# LaserController.net
KiCad netlist of a schematic drawn in Altium Designer
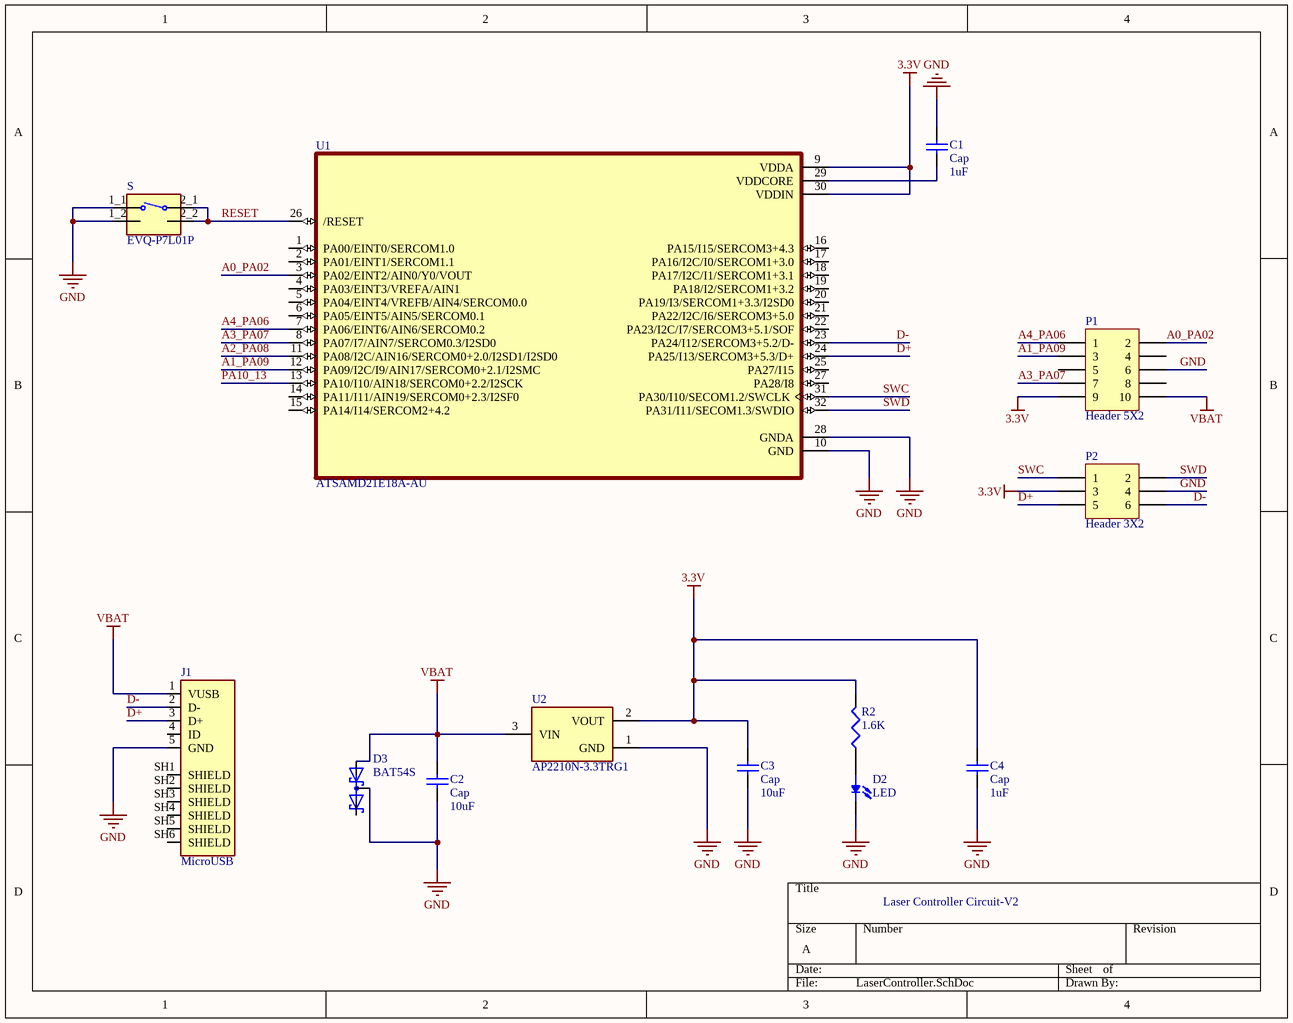
[diagram p0: LaserController.SchDoc]

(export (version "E")
  (design (tool "Eeschema 10.0.6"))
  (components
    (comp (ref "C1")
      (value "Cap")
      (footprint "6-0805_M")
      (description "Capacitor")
      (fields (field (name "ALTIUM_VALUE") "1uF") (field (name "PUBLISHER") "Altium Limited"))
      (libsource (lib "Miscellaneous Devices") (part "Cap"))
    )
    (comp (ref "C2")
      (value "Cap")
      (footprint "6-0805_M")
      (description "Capacitor")
      (fields (field (name "ALTIUM_VALUE") "10uF") (field (name "PUBLISHER") "Altium Limited"))
      (libsource (lib "Miscellaneous Devices") (part "Cap"))
    )
    (comp (ref "C3")
      (value "Cap")
      (footprint "6-0805_M")
      (description "Capacitor")
      (fields (field (name "ALTIUM_VALUE") "10uF") (field (name "PUBLISHER") "Altium Limited"))
      (libsource (lib "Miscellaneous Devices") (part "Cap"))
    )
    (comp (ref "C4")
      (value "Cap")
      (footprint "6-0805_M")
      (description "Capacitor")
      (fields (field (name "ALTIUM_VALUE") "1uF") (field (name "PUBLISHER") "Altium Limited"))
      (libsource (lib "Miscellaneous Devices") (part "Cap"))
    )
    (comp (ref "D2")
      (value "LED")
      (footprint "DIO_SMLMN2WB1CW1C")
      (description "White LED Indication - Discrete 2.9V 0805 _2012 Metric_")
      (fields (field (name "MP") "SMLMN2WB1CW1C") (field (name "MF") "Rohm Semiconductor"))
      (libsource (lib "SMLMN2WB1CW1C") (part "SMLMN2WB1CW1C"))
    )
    (comp (ref "D3")
      (value "BAT54S")
      (footprint "SnapEDApcb:SOT23")
      (description "Diode Array 1 Pair Series Connection Schottky 30V 200mA Surface Mount TO-236-3, SC-59, SOT-23-3")
      (fields (field (name "MF") "ON Semiconductor"))
      (libsource (lib "BAT54S") (part "BAT54S"))
    )
    (comp (ref "J1")
      (value "MicroUSB")
      (footprint "AMPHENOL_10118192-0001LF")
      (description "USB - micro B USB 2.0 Receptacle Connector 5 Position Surface Mount, Right Angle")
      (fields (field (name "MP") "10118192-0001LF") (field (name "MF") "Amphenol ICC"))
      (libsource (lib "MicroUSB_2") (part "10118192-0001LF"))
    )
    (comp (ref "P1")
      (value "Header 5X2")
      (footprint "HDR2X5")
      (description "Header, 5-Pin, Dual row")
      (fields (field (name "PUBLISHER") "Altium Limited"))
      (libsource (lib "Miscellaneous Connectors") (part "Header 5X2"))
    )
    (comp (ref "P2")
      (value "Header 3X2")
      (footprint "HDR2X3")
      (description "Header, 3-Pin, Dual row")
      (fields (field (name "PUBLISHER") "Altium Limited"))
      (libsource (lib "Miscellaneous Connectors") (part "Header 3X2"))
    )
    (comp (ref "R2")
      (value "1.6K")
      (footprint "6-0805_M")
      (description "Resistor")
      (fields (field (name "PUBLISHER") "Altium Limited"))
      (libsource (lib "Miscellaneous Devices") (part "Res3"))
    )
    (comp (ref "S")
      (value "EVQ-P7L01P")
      (footprint "SW_EVQ-P7L01P")
      (description "Tactile Switch SPST-NO Side Actuated Surface Mount, Right Angle")
      (fields
        (field (name "DIGI-KEY_PART_NUMBER") "P16769CT-ND")
        (field (name "MF") "Panasonic Electronic Components")
      )
      (libsource (lib "EVQ-P7L01P") (part "EVQ-P7L01P"))
    )
    (comp (ref "U1")
      (value "ATSAMD21E18A-AU")
      (footprint "QFP80P900X900X120-32N:QFP80P900X900X120-32N")
      (description "ARM庐 Cortex庐-M0+ SAM D21E Microcontroller IC 32-Bit 48MHz 256KB (256K x 8) FLASH 32-TQFP (7x7)")
      (fields (field (name "MF") "Microchip"))
      (libsource (lib "SAMD21") (part "ATSAMD21E18A-AU"))
    )
    (comp (ref "U2")
      (value "AP2210N-3.3TRG1")
      (footprint "SOT95P280X145-3N")
      (description "Linear Voltage Regulator IC 1 Output 300mA SOT-23-3")
      (fields (field (name "MF") "Diodes Inc."))
      (libsource (lib "AP2210N-3.3TRG1") (part "AP2210N-3.3TRG1"))
    )
  )
  (nets
    (net (code "1") (name "/A0_PA02") (class "Default")
      (node (ref "P1") (pin "2") (pinfunction "2_2") (pintype "passive"))
      (node (ref "U1") (pin "3") (pinfunction "PA02/EINT2/AIN0/Y0/VOUT_3") (pintype "bidirectional"))
    )
    (net (code "2") (name "/A1_PA09") (class "Default")
      (node (ref "P1") (pin "3") (pinfunction "3_3") (pintype "passive"))
      (node (ref "U1") (pin "12") (pinfunction "PA09/I2C/I9/AIN17/SERCOM0+2.1/I2SMC_12") (pintype "bidirectional"))
    )
    (net (code "3") (name "/A2_PA08") (class "Default")
      (node (ref "U1") (pin "11") (pinfunction "PA08/I2C/AIN16/SERCOM0+2.0/I2SD1/I2SD0_11") (pintype "bidirectional"))
    )
    (net (code "4") (name "/A3_PA07") (class "Default")
      (node (ref "P1") (pin "7") (pinfunction "7_7") (pintype "passive"))
      (node (ref "U1") (pin "8") (pinfunction "PA07/I7/AIN7/SERCOM0.3/I2SD0_8") (pintype "bidirectional"))
    )
    (net (code "5") (name "/A4_PA06") (class "Default")
      (node (ref "P1") (pin "1") (pinfunction "1_1") (pintype "passive"))
      (node (ref "U1") (pin "7") (pinfunction "PA06/EINT6/AIN6/SERCOM0.2_7") (pintype "bidirectional"))
    )
    (net (code "6") (name "/D+") (class "Default")
      (node (ref "J1") (pin "3") (pinfunction "D+_3") (pintype "passive"))
      (node (ref "P2") (pin "5") (pinfunction "5_5") (pintype "passive"))
      (node (ref "U1") (pin "24") (pinfunction "PA25/I13/SERCOM3+5.3/D+_24") (pintype "bidirectional"))
    )
    (net (code "7") (name "/D-") (class "Default")
      (node (ref "J1") (pin "2") (pinfunction "D-_2") (pintype "passive"))
      (node (ref "P2") (pin "6") (pinfunction "6_6") (pintype "passive"))
      (node (ref "U1") (pin "23") (pinfunction "PA24/I12/SERCOM3+5.2/D-_23") (pintype "bidirectional"))
    )
    (net (code "8") (name "/PA10_13") (class "Default")
      (node (ref "U1") (pin "13") (pinfunction "PA10/I10/AIN18/SERCOM0+2.2/I2SCK_13") (pintype "bidirectional"))
    )
    (net (code "9") (name "/RESET") (class "Default")
      (node (ref "S") (pin "2_1") (pinfunction "2_2_1") (pintype "passive"))
      (node (ref "S") (pin "2_2") (pinfunction "2_2_2") (pintype "passive"))
      (node (ref "U1") (pin "26") (pinfunction "/RESET_26") (pintype "bidirectional"))
    )
    (net (code "10") (name "/SWC") (class "Default")
      (node (ref "P2") (pin "1") (pinfunction "1_1") (pintype "passive"))
      (node (ref "U1") (pin "31") (pinfunction "PA30/I10/SECOM1.2/SWCLK_31") (pintype "bidirectional"))
    )
    (net (code "11") (name "/SWD") (class "Default")
      (node (ref "P2") (pin "2") (pinfunction "2_2") (pintype "passive"))
      (node (ref "U1") (pin "32") (pinfunction "PA31/I11/SECOM1.3/SWDIO_32") (pintype "bidirectional"))
    )
    (net (code "12") (name "3.3V") (class "Default")
      (node (ref "C3") (pin "2") (pinfunction "2_2") (pintype "passive"))
      (node (ref "C4") (pin "2") (pinfunction "2_2") (pintype "passive"))
      (node (ref "P1") (pin "9") (pinfunction "9_9") (pintype "passive"))
      (node (ref "P2") (pin "3") (pinfunction "3_3") (pintype "passive"))
      (node (ref "R2") (pin "2") (pinfunction "2_2") (pintype "passive"))
      (node (ref "U1") (pin "30") (pinfunction "VDDIN_30") (pintype "power_in"))
      (node (ref "U1") (pin "9") (pinfunction "VDDA_9") (pintype "power_in"))
      (node (ref "U2") (pin "2") (pinfunction "VOUT_2") (pintype "passive"))
    )
    (net (code "13") (name "GND") (class "Default")
      (node (ref "C1") (pin "2") (pinfunction "2_2") (pintype "passive"))
      (node (ref "C2") (pin "1") (pinfunction "1_1") (pintype "passive"))
      (node (ref "C3") (pin "1") (pinfunction "1_1") (pintype "passive"))
      (node (ref "C4") (pin "1") (pinfunction "1_1") (pintype "passive"))
      (node (ref "D2") (pin "C") (pinfunction "C_C") (pintype "passive"))
      (node (ref "D3") (pin "3") (pinfunction "K1A2_3") (pintype "passive"))
      (node (ref "J1") (pin "5") (pinfunction "GND_5") (pintype "passive"))
      (node (ref "P1") (pin "6") (pinfunction "6_6") (pintype "passive"))
      (node (ref "P2") (pin "4") (pinfunction "4_4") (pintype "passive"))
      (node (ref "S") (pin "1_1") (pinfunction "1_1_1") (pintype "passive"))
      (node (ref "S") (pin "1_2") (pinfunction "1_1_2") (pintype "passive"))
      (node (ref "U1") (pin "10") (pinfunction "GND_10") (pintype "power_in"))
      (node (ref "U1") (pin "28") (pinfunction "GNDA_28") (pintype "power_in"))
      (node (ref "U2") (pin "1") (pinfunction "GND_1") (pintype "passive"))
    )
    (net (code "14") (name "Net-(D2-PadA)") (class "Default")
      (node (ref "D2") (pin "A") (pinfunction "A_A") (pintype "passive"))
      (node (ref "R2") (pin "1") (pinfunction "1_1") (pintype "passive"))
    )
    (net (code "15") (name "Net-(U1-VDDCORE)") (class "Default")
      (node (ref "C1") (pin "1") (pinfunction "1_1") (pintype "passive"))
      (node (ref "U1") (pin "29") (pinfunction "VDDCORE_29") (pintype "power_in"))
    )
    (net (code "16") (name "VBAT") (class "Default")
      (node (ref "C2") (pin "2") (pinfunction "2_2") (pintype "passive"))
      (node (ref "D3") (pin "1") (pinfunction "A1_1") (pintype "passive"))
      (node (ref "J1") (pin "1") (pinfunction "VUSB_1") (pintype "passive"))
      (node (ref "P1") (pin "10") (pinfunction "10_10") (pintype "passive"))
      (node (ref "U2") (pin "3") (pinfunction "VIN_3") (pintype "passive"))
    )
    (net (code "17") (name "unconnected-(D3-K2-Pad2)") (class "Default")
      (node (ref "D3") (pin "2") (pinfunction "K2_2") (pintype "passive"))
    )
    (net (code "18") (name "unconnected-(J1-ID-Pad4)") (class "Default")
      (node (ref "J1") (pin "4") (pinfunction "ID_4") (pintype "passive"))
    )
    (net (code "19") (name "unconnected-(J1-SHIELD-PadSH1)") (class "Default")
      (node (ref "J1") (pin "SH1") (pinfunction "SHIELD_SH1") (pintype "passive"))
    )
    (net (code "20") (name "unconnected-(J1-SHIELD-PadSH2)") (class "Default")
      (node (ref "J1") (pin "SH2") (pinfunction "SHIELD_SH2") (pintype "passive"))
    )
    (net (code "21") (name "unconnected-(J1-SHIELD-PadSH3)") (class "Default")
      (node (ref "J1") (pin "SH3") (pinfunction "SHIELD_SH3") (pintype "passive"))
    )
    (net (code "22") (name "unconnected-(J1-SHIELD-PadSH4)") (class "Default")
      (node (ref "J1") (pin "SH4") (pinfunction "SHIELD_SH4") (pintype "passive"))
    )
    (net (code "23") (name "unconnected-(J1-SHIELD-PadSH5)") (class "Default")
      (node (ref "J1") (pin "SH5") (pinfunction "SHIELD_SH5") (pintype "passive"))
    )
    (net (code "24") (name "unconnected-(J1-SHIELD-PadSH6)") (class "Default")
      (node (ref "J1") (pin "SH6") (pinfunction "SHIELD_SH6") (pintype "passive"))
    )
    (net (code "25") (name "unconnected-(P1-Pad4)") (class "Default")
      (node (ref "P1") (pin "4") (pinfunction "4_4") (pintype "passive"))
    )
    (net (code "26") (name "unconnected-(P1-Pad5)") (class "Default")
      (node (ref "P1") (pin "5") (pinfunction "5_5") (pintype "passive"))
    )
    (net (code "27") (name "unconnected-(P1-Pad8)") (class "Default")
      (node (ref "P1") (pin "8") (pinfunction "8_8") (pintype "passive"))
    )
    (net (code "28") (name "unconnected-(U1-PA00{slash}EINT0{slash}SERCOM1.0-Pad1)") (class "Default")
      (node (ref "U1") (pin "1") (pinfunction "PA00/EINT0/SERCOM1.0_1") (pintype "bidirectional"))
    )
    (net (code "29") (name "unconnected-(U1-PA01{slash}EINT1{slash}SERCOM1.1-Pad2)") (class "Default")
      (node (ref "U1") (pin "2") (pinfunction "PA01/EINT1/SERCOM1.1_2") (pintype "bidirectional"))
    )
    (net (code "30") (name "unconnected-(U1-PA03{slash}EINT3{slash}VREFA{slash}AIN1-Pad4)") (class "Default")
      (node (ref "U1") (pin "4") (pinfunction "PA03/EINT3/VREFA/AIN1_4") (pintype "bidirectional"))
    )
    (net (code "31") (name "unconnected-(U1-PA04{slash}EINT4{slash}VREFB{slash}AIN4{slash}SERCOM0.0-Pad5)") (class "Default")
      (node (ref "U1") (pin "5") (pinfunction "PA04/EINT4/VREFB/AIN4/SERCOM0.0_5") (pintype "bidirectional"))
    )
    (net (code "32") (name "unconnected-(U1-PA05{slash}EINT5{slash}AIN5{slash}SERCOM0.1-Pad6)") (class "Default")
      (node (ref "U1") (pin "6") (pinfunction "PA05/EINT5/AIN5/SERCOM0.1_6") (pintype "bidirectional"))
    )
    (net (code "33") (name "unconnected-(U1-PA11{slash}I11{slash}AIN19{slash}SERCOM0+2.3{slash}I2SF0-Pad14)") (class "Default")
      (node (ref "U1") (pin "14") (pinfunction "PA11/I11/AIN19/SERCOM0+2.3/I2SF0_14") (pintype "bidirectional"))
    )
    (net (code "34") (name "unconnected-(U1-PA14{slash}I14{slash}SERCOM2+4.2-Pad15)") (class "Default")
      (node (ref "U1") (pin "15") (pinfunction "PA14/I14/SERCOM2+4.2_15") (pintype "bidirectional"))
    )
    (net (code "35") (name "unconnected-(U1-PA15{slash}I15{slash}SERCOM3+4.3-Pad16)") (class "Default")
      (node (ref "U1") (pin "16") (pinfunction "PA15/I15/SERCOM3+4.3_16") (pintype "bidirectional"))
    )
    (net (code "36") (name "unconnected-(U1-PA16{slash}I2C{slash}I0{slash}SERCOM1+3.0-Pad17)") (class "Default")
      (node (ref "U1") (pin "17") (pinfunction "PA16/I2C/I0/SERCOM1+3.0_17") (pintype "bidirectional"))
    )
    (net (code "37") (name "unconnected-(U1-PA17{slash}I2C{slash}I1{slash}SERCOM1+3.1-Pad18)") (class "Default")
      (node (ref "U1") (pin "18") (pinfunction "PA17/I2C/I1/SERCOM1+3.1_18") (pintype "bidirectional"))
    )
    (net (code "38") (name "unconnected-(U1-PA18{slash}I2{slash}SERCOM1+3.2-Pad19)") (class "Default")
      (node (ref "U1") (pin "19") (pinfunction "PA18/I2/SERCOM1+3.2_19") (pintype "bidirectional"))
    )
    (net (code "39") (name "unconnected-(U1-PA19{slash}I3{slash}SERCOM1+3.3{slash}I2SD0-Pad20)") (class "Default")
      (node (ref "U1") (pin "20") (pinfunction "PA19/I3/SERCOM1+3.3/I2SD0_20") (pintype "bidirectional"))
    )
    (net (code "40") (name "unconnected-(U1-PA22{slash}I2C{slash}I6{slash}SERCOM3+5.0-Pad21)") (class "Default")
      (node (ref "U1") (pin "21") (pinfunction "PA22/I2C/I6/SERCOM3+5.0_21") (pintype "bidirectional"))
    )
    (net (code "41") (name "unconnected-(U1-PA23{slash}I2C{slash}I7{slash}SERCOM3+5.1{slash}SOF-Pad22)") (class "Default")
      (node (ref "U1") (pin "22") (pinfunction "PA23/I2C/I7/SERCOM3+5.1/SOF_22") (pintype "bidirectional"))
    )
    (net (code "42") (name "unconnected-(U1-PA27{slash}I15-Pad25)") (class "Default")
      (node (ref "U1") (pin "25") (pinfunction "PA27/I15_25") (pintype "bidirectional"))
    )
    (net (code "43") (name "unconnected-(U1-PA28{slash}I8-Pad27)") (class "Default")
      (node (ref "U1") (pin "27") (pinfunction "PA28/I8_27") (pintype "bidirectional"))
    )
  )
)
